# BBB_ADS1271_front_panel.net
KiCad netlist of a schematic drawn in EAGLE
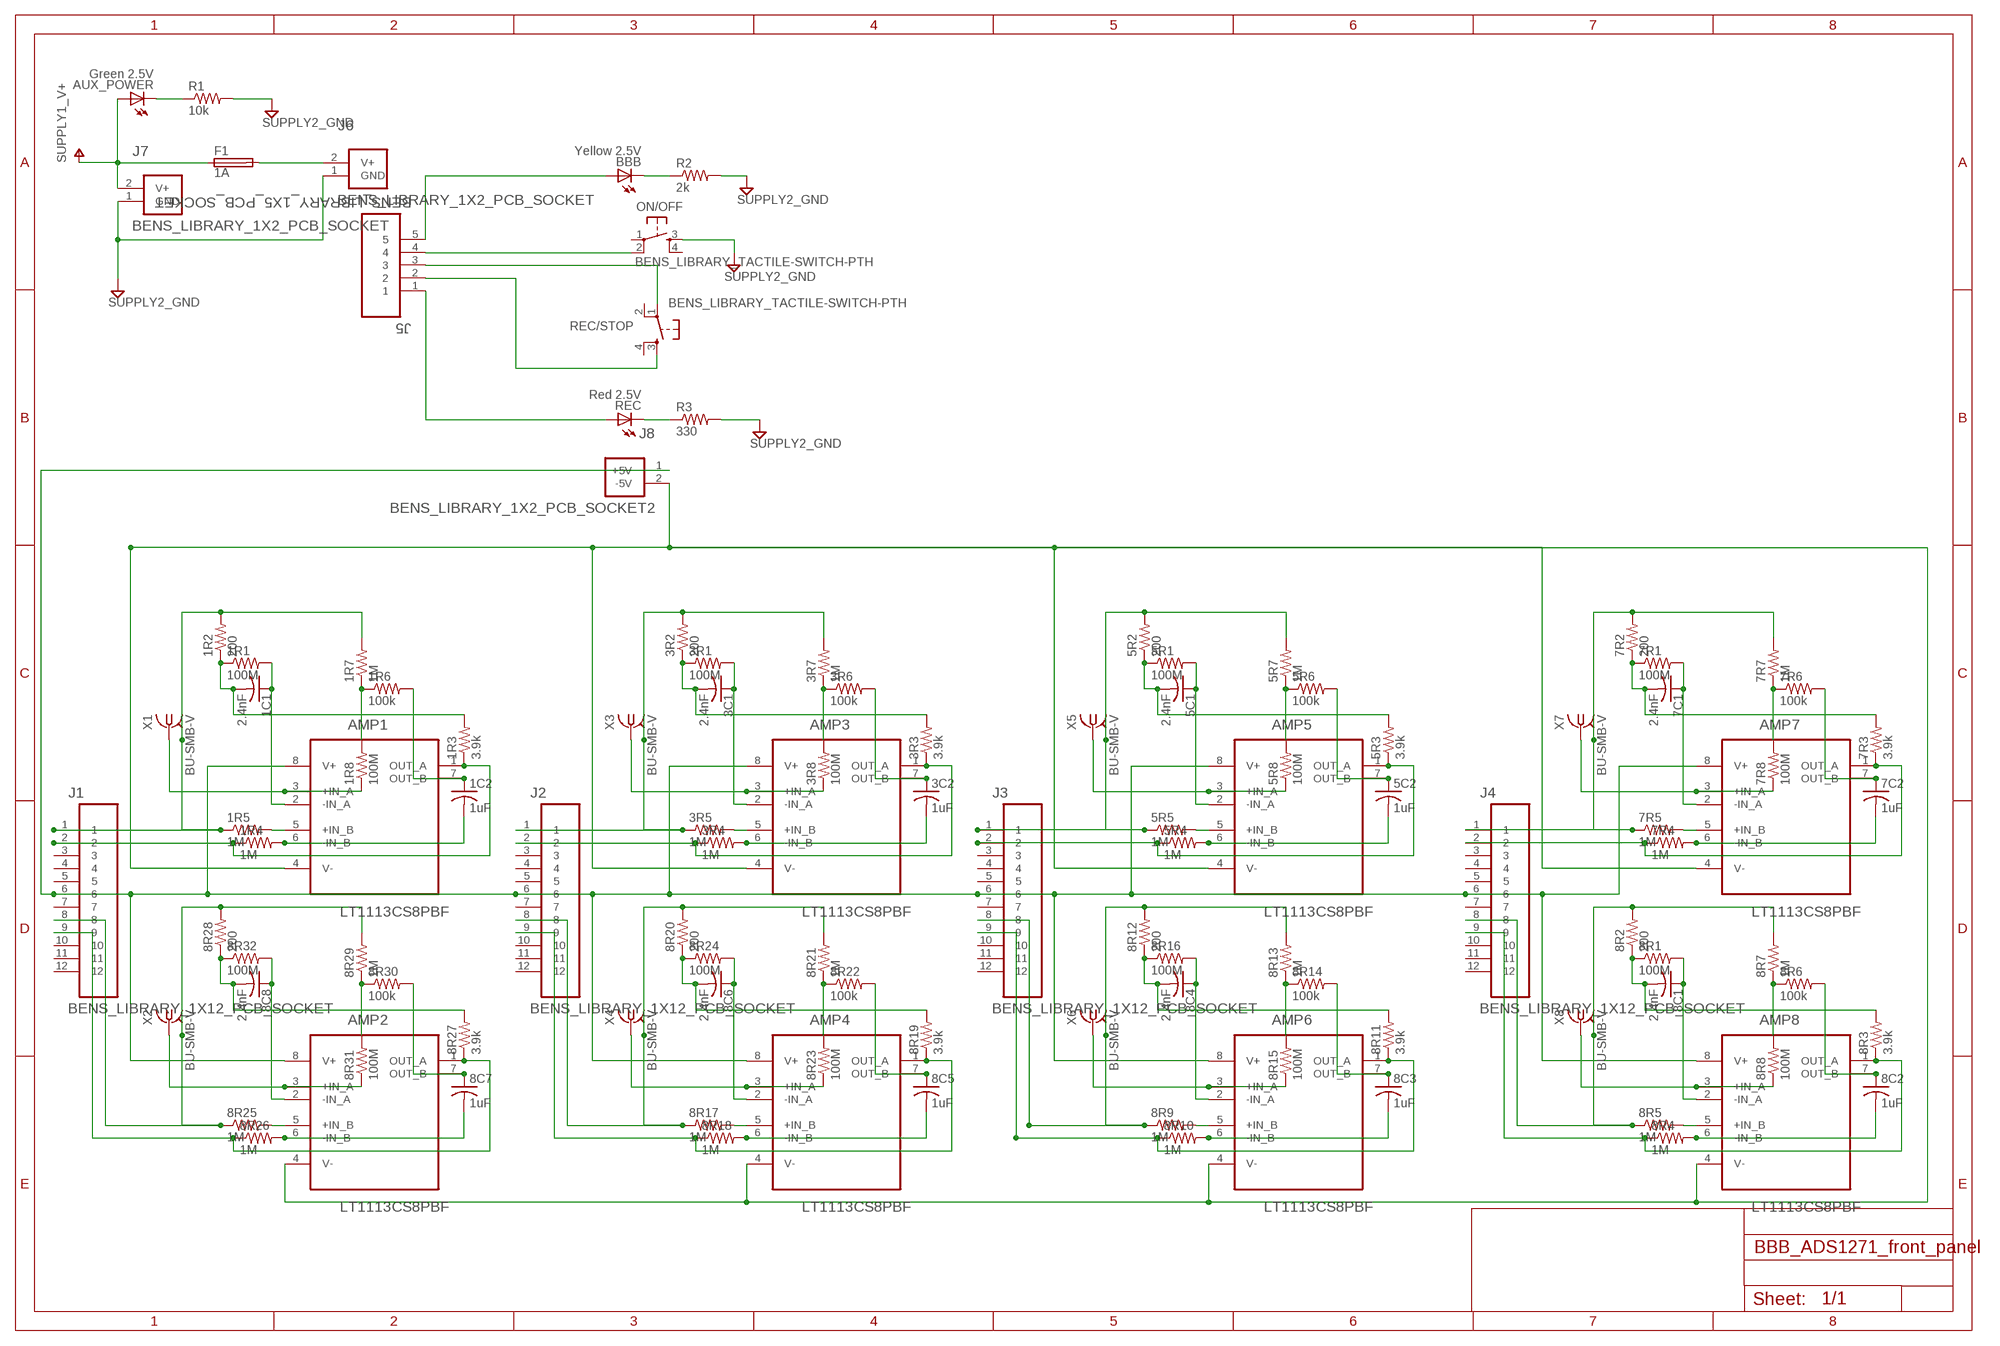
[diagram p0: schematic, sheet 1]

(export (version "E")
  (design (tool "Eeschema 10.0.6"))
  (components
    (comp (ref "1C1")
      (value "2.4nF")
      (footprint "eagle-import:ADAFRUIT_C0805K")
      (libsource (lib "eagle-import") (part "ADAFRUIT_C-USC0805K"))
    )
    (comp (ref "1C2")
      (value "1uF")
      (footprint "eagle-import:ADAFRUIT_C0805K")
      (libsource (lib "eagle-import") (part "ADAFRUIT_C-USC0805K"))
    )
    (comp (ref "1R1")
      (value "100M")
      (footprint "eagle-import:ADAFRUIT_R0805")
      (libsource (lib "eagle-import") (part "ADAFRUIT_R-US_R0805"))
    )
    (comp (ref "1R2")
      (value "200")
      (footprint "eagle-import:ADAFRUIT_R0805")
      (libsource (lib "eagle-import") (part "ADAFRUIT_R-US_R0805"))
    )
    (comp (ref "1R3")
      (value "3.9k")
      (footprint "eagle-import:ADAFRUIT_R0805")
      (libsource (lib "eagle-import") (part "ADAFRUIT_R-US_R0805"))
    )
    (comp (ref "1R4")
      (value "1M")
      (footprint "eagle-import:ADAFRUIT_R0805")
      (libsource (lib "eagle-import") (part "ADAFRUIT_R-US_R0805"))
    )
    (comp (ref "1R5")
      (value "1M")
      (footprint "eagle-import:ADAFRUIT_R0805")
      (libsource (lib "eagle-import") (part "ADAFRUIT_R-US_R0805"))
    )
    (comp (ref "1R6")
      (value "100k")
      (footprint "eagle-import:ADAFRUIT_R0805")
      (libsource (lib "eagle-import") (part "ADAFRUIT_R-US_R0805"))
    )
    (comp (ref "1R7")
      (value "1M")
      (footprint "eagle-import:ADAFRUIT_R0805")
      (libsource (lib "eagle-import") (part "ADAFRUIT_R-US_R0805"))
    )
    (comp (ref "1R8")
      (value "100M")
      (footprint "eagle-import:ADAFRUIT_R0805")
      (libsource (lib "eagle-import") (part "ADAFRUIT_R-US_R0805"))
    )
    (comp (ref "3C1")
      (value "2.4nF")
      (footprint "eagle-import:ADAFRUIT_C0805K")
      (libsource (lib "eagle-import") (part "ADAFRUIT_C-USC0805K"))
    )
    (comp (ref "3C2")
      (value "1uF")
      (footprint "eagle-import:ADAFRUIT_C0805K")
      (libsource (lib "eagle-import") (part "ADAFRUIT_C-USC0805K"))
    )
    (comp (ref "3R1")
      (value "100M")
      (footprint "eagle-import:ADAFRUIT_R0805")
      (libsource (lib "eagle-import") (part "ADAFRUIT_R-US_R0805"))
    )
    (comp (ref "3R2")
      (value "200")
      (footprint "eagle-import:ADAFRUIT_R0805")
      (libsource (lib "eagle-import") (part "ADAFRUIT_R-US_R0805"))
    )
    (comp (ref "3R3")
      (value "3.9k")
      (footprint "eagle-import:ADAFRUIT_R0805")
      (libsource (lib "eagle-import") (part "ADAFRUIT_R-US_R0805"))
    )
    (comp (ref "3R4")
      (value "1M")
      (footprint "eagle-import:ADAFRUIT_R0805")
      (libsource (lib "eagle-import") (part "ADAFRUIT_R-US_R0805"))
    )
    (comp (ref "3R5")
      (value "1M")
      (footprint "eagle-import:ADAFRUIT_R0805")
      (libsource (lib "eagle-import") (part "ADAFRUIT_R-US_R0805"))
    )
    (comp (ref "3R6")
      (value "100k")
      (footprint "eagle-import:ADAFRUIT_R0805")
      (libsource (lib "eagle-import") (part "ADAFRUIT_R-US_R0805"))
    )
    (comp (ref "3R7")
      (value "1M")
      (footprint "eagle-import:ADAFRUIT_R0805")
      (libsource (lib "eagle-import") (part "ADAFRUIT_R-US_R0805"))
    )
    (comp (ref "3R8")
      (value "100M")
      (footprint "eagle-import:ADAFRUIT_R0805")
      (libsource (lib "eagle-import") (part "ADAFRUIT_R-US_R0805"))
    )
    (comp (ref "5C1")
      (value "2.4nF")
      (footprint "eagle-import:ADAFRUIT_C0805K")
      (libsource (lib "eagle-import") (part "ADAFRUIT_C-USC0805K"))
    )
    (comp (ref "5C2")
      (value "1uF")
      (footprint "eagle-import:ADAFRUIT_C0805K")
      (libsource (lib "eagle-import") (part "ADAFRUIT_C-USC0805K"))
    )
    (comp (ref "5R1")
      (value "100M")
      (footprint "eagle-import:ADAFRUIT_R0805")
      (libsource (lib "eagle-import") (part "ADAFRUIT_R-US_R0805"))
    )
    (comp (ref "5R2")
      (value "200")
      (footprint "eagle-import:ADAFRUIT_R0805")
      (libsource (lib "eagle-import") (part "ADAFRUIT_R-US_R0805"))
    )
    (comp (ref "5R3")
      (value "3.9k")
      (footprint "eagle-import:ADAFRUIT_R0805")
      (libsource (lib "eagle-import") (part "ADAFRUIT_R-US_R0805"))
    )
    (comp (ref "5R4")
      (value "1M")
      (footprint "eagle-import:ADAFRUIT_R0805")
      (libsource (lib "eagle-import") (part "ADAFRUIT_R-US_R0805"))
    )
    (comp (ref "5R5")
      (value "1M")
      (footprint "eagle-import:ADAFRUIT_R0805")
      (libsource (lib "eagle-import") (part "ADAFRUIT_R-US_R0805"))
    )
    (comp (ref "5R6")
      (value "100k")
      (footprint "eagle-import:ADAFRUIT_R0805")
      (libsource (lib "eagle-import") (part "ADAFRUIT_R-US_R0805"))
    )
    (comp (ref "5R7")
      (value "1M")
      (footprint "eagle-import:ADAFRUIT_R0805")
      (libsource (lib "eagle-import") (part "ADAFRUIT_R-US_R0805"))
    )
    (comp (ref "5R8")
      (value "100M")
      (footprint "eagle-import:ADAFRUIT_R0805")
      (libsource (lib "eagle-import") (part "ADAFRUIT_R-US_R0805"))
    )
    (comp (ref "7C1")
      (value "2.4nF")
      (footprint "eagle-import:ADAFRUIT_C0805K")
      (libsource (lib "eagle-import") (part "ADAFRUIT_C-USC0805K"))
    )
    (comp (ref "7C2")
      (value "1uF")
      (footprint "eagle-import:ADAFRUIT_C0805K")
      (libsource (lib "eagle-import") (part "ADAFRUIT_C-USC0805K"))
    )
    (comp (ref "7R1")
      (value "100M")
      (footprint "eagle-import:ADAFRUIT_R0805")
      (libsource (lib "eagle-import") (part "ADAFRUIT_R-US_R0805"))
    )
    (comp (ref "7R2")
      (value "200")
      (footprint "eagle-import:ADAFRUIT_R0805")
      (libsource (lib "eagle-import") (part "ADAFRUIT_R-US_R0805"))
    )
    (comp (ref "7R3")
      (value "3.9k")
      (footprint "eagle-import:ADAFRUIT_R0805")
      (libsource (lib "eagle-import") (part "ADAFRUIT_R-US_R0805"))
    )
    (comp (ref "7R4")
      (value "1M")
      (footprint "eagle-import:ADAFRUIT_R0805")
      (libsource (lib "eagle-import") (part "ADAFRUIT_R-US_R0805"))
    )
    (comp (ref "7R5")
      (value "1M")
      (footprint "eagle-import:ADAFRUIT_R0805")
      (libsource (lib "eagle-import") (part "ADAFRUIT_R-US_R0805"))
    )
    (comp (ref "7R6")
      (value "100k")
      (footprint "eagle-import:ADAFRUIT_R0805")
      (libsource (lib "eagle-import") (part "ADAFRUIT_R-US_R0805"))
    )
    (comp (ref "7R7")
      (value "1M")
      (footprint "eagle-import:ADAFRUIT_R0805")
      (libsource (lib "eagle-import") (part "ADAFRUIT_R-US_R0805"))
    )
    (comp (ref "7R8")
      (value "100M")
      (footprint "eagle-import:ADAFRUIT_R0805")
      (libsource (lib "eagle-import") (part "ADAFRUIT_R-US_R0805"))
    )
    (comp (ref "8C1")
      (value "2.4nF")
      (footprint "eagle-import:ADAFRUIT_C0805K")
      (libsource (lib "eagle-import") (part "ADAFRUIT_C-USC0805K"))
    )
    (comp (ref "8C2")
      (value "1uF")
      (footprint "eagle-import:ADAFRUIT_C0805K")
      (libsource (lib "eagle-import") (part "ADAFRUIT_C-USC0805K"))
    )
    (comp (ref "8C3")
      (value "1uF")
      (footprint "eagle-import:ADAFRUIT_C0805K")
      (libsource (lib "eagle-import") (part "ADAFRUIT_C-USC0805K"))
    )
    (comp (ref "8C4")
      (value "2.4nF")
      (footprint "eagle-import:ADAFRUIT_C0805K")
      (libsource (lib "eagle-import") (part "ADAFRUIT_C-USC0805K"))
    )
    (comp (ref "8C5")
      (value "1uF")
      (footprint "eagle-import:ADAFRUIT_C0805K")
      (libsource (lib "eagle-import") (part "ADAFRUIT_C-USC0805K"))
    )
    (comp (ref "8C6")
      (value "2.4nF")
      (footprint "eagle-import:ADAFRUIT_C0805K")
      (libsource (lib "eagle-import") (part "ADAFRUIT_C-USC0805K"))
    )
    (comp (ref "8C7")
      (value "1uF")
      (footprint "eagle-import:ADAFRUIT_C0805K")
      (libsource (lib "eagle-import") (part "ADAFRUIT_C-USC0805K"))
    )
    (comp (ref "8C8")
      (value "2.4nF")
      (footprint "eagle-import:ADAFRUIT_C0805K")
      (libsource (lib "eagle-import") (part "ADAFRUIT_C-USC0805K"))
    )
    (comp (ref "8R1")
      (value "100M")
      (footprint "eagle-import:ADAFRUIT_R0805")
      (libsource (lib "eagle-import") (part "ADAFRUIT_R-US_R0805"))
    )
    (comp (ref "8R2")
      (value "200")
      (footprint "eagle-import:ADAFRUIT_R0805")
      (libsource (lib "eagle-import") (part "ADAFRUIT_R-US_R0805"))
    )
    (comp (ref "8R3")
      (value "3.9k")
      (footprint "eagle-import:ADAFRUIT_R0805")
      (libsource (lib "eagle-import") (part "ADAFRUIT_R-US_R0805"))
    )
    (comp (ref "8R4")
      (value "1M")
      (footprint "eagle-import:ADAFRUIT_R0805")
      (libsource (lib "eagle-import") (part "ADAFRUIT_R-US_R0805"))
    )
    (comp (ref "8R5")
      (value "1M")
      (footprint "eagle-import:ADAFRUIT_R0805")
      (libsource (lib "eagle-import") (part "ADAFRUIT_R-US_R0805"))
    )
    (comp (ref "8R6")
      (value "100k")
      (footprint "eagle-import:ADAFRUIT_R0805")
      (libsource (lib "eagle-import") (part "ADAFRUIT_R-US_R0805"))
    )
    (comp (ref "8R7")
      (value "1M")
      (footprint "eagle-import:ADAFRUIT_R0805")
      (libsource (lib "eagle-import") (part "ADAFRUIT_R-US_R0805"))
    )
    (comp (ref "8R8")
      (value "100M")
      (footprint "eagle-import:ADAFRUIT_R0805")
      (libsource (lib "eagle-import") (part "ADAFRUIT_R-US_R0805"))
    )
    (comp (ref "8R9")
      (value "1M")
      (footprint "eagle-import:ADAFRUIT_R0805")
      (libsource (lib "eagle-import") (part "ADAFRUIT_R-US_R0805"))
    )
    (comp (ref "8R10")
      (value "1M")
      (footprint "eagle-import:ADAFRUIT_R0805")
      (libsource (lib "eagle-import") (part "ADAFRUIT_R-US_R0805"))
    )
    (comp (ref "8R11")
      (value "3.9k")
      (footprint "eagle-import:ADAFRUIT_R0805")
      (libsource (lib "eagle-import") (part "ADAFRUIT_R-US_R0805"))
    )
    (comp (ref "8R12")
      (value "200")
      (footprint "eagle-import:ADAFRUIT_R0805")
      (libsource (lib "eagle-import") (part "ADAFRUIT_R-US_R0805"))
    )
    (comp (ref "8R13")
      (value "1M")
      (footprint "eagle-import:ADAFRUIT_R0805")
      (libsource (lib "eagle-import") (part "ADAFRUIT_R-US_R0805"))
    )
    (comp (ref "8R14")
      (value "100k")
      (footprint "eagle-import:ADAFRUIT_R0805")
      (libsource (lib "eagle-import") (part "ADAFRUIT_R-US_R0805"))
    )
    (comp (ref "8R15")
      (value "100M")
      (footprint "eagle-import:ADAFRUIT_R0805")
      (libsource (lib "eagle-import") (part "ADAFRUIT_R-US_R0805"))
    )
    (comp (ref "8R16")
      (value "100M")
      (footprint "eagle-import:ADAFRUIT_R0805")
      (libsource (lib "eagle-import") (part "ADAFRUIT_R-US_R0805"))
    )
    (comp (ref "8R17")
      (value "1M")
      (footprint "eagle-import:ADAFRUIT_R0805")
      (libsource (lib "eagle-import") (part "ADAFRUIT_R-US_R0805"))
    )
    (comp (ref "8R18")
      (value "1M")
      (footprint "eagle-import:ADAFRUIT_R0805")
      (libsource (lib "eagle-import") (part "ADAFRUIT_R-US_R0805"))
    )
    (comp (ref "8R19")
      (value "3.9k")
      (footprint "eagle-import:ADAFRUIT_R0805")
      (libsource (lib "eagle-import") (part "ADAFRUIT_R-US_R0805"))
    )
    (comp (ref "8R20")
      (value "200")
      (footprint "eagle-import:ADAFRUIT_R0805")
      (libsource (lib "eagle-import") (part "ADAFRUIT_R-US_R0805"))
    )
    (comp (ref "8R21")
      (value "1M")
      (footprint "eagle-import:ADAFRUIT_R0805")
      (libsource (lib "eagle-import") (part "ADAFRUIT_R-US_R0805"))
    )
    (comp (ref "8R22")
      (value "100k")
      (footprint "eagle-import:ADAFRUIT_R0805")
      (libsource (lib "eagle-import") (part "ADAFRUIT_R-US_R0805"))
    )
    (comp (ref "8R23")
      (value "100M")
      (footprint "eagle-import:ADAFRUIT_R0805")
      (libsource (lib "eagle-import") (part "ADAFRUIT_R-US_R0805"))
    )
    (comp (ref "8R24")
      (value "100M")
      (footprint "eagle-import:ADAFRUIT_R0805")
      (libsource (lib "eagle-import") (part "ADAFRUIT_R-US_R0805"))
    )
    (comp (ref "8R25")
      (value "1M")
      (footprint "eagle-import:ADAFRUIT_R0805")
      (libsource (lib "eagle-import") (part "ADAFRUIT_R-US_R0805"))
    )
    (comp (ref "8R26")
      (value "1M")
      (footprint "eagle-import:ADAFRUIT_R0805")
      (libsource (lib "eagle-import") (part "ADAFRUIT_R-US_R0805"))
    )
    (comp (ref "8R27")
      (value "3.9k")
      (footprint "eagle-import:ADAFRUIT_R0805")
      (libsource (lib "eagle-import") (part "ADAFRUIT_R-US_R0805"))
    )
    (comp (ref "8R28")
      (value "200")
      (footprint "eagle-import:ADAFRUIT_R0805")
      (libsource (lib "eagle-import") (part "ADAFRUIT_R-US_R0805"))
    )
    (comp (ref "8R29")
      (value "1M")
      (footprint "eagle-import:ADAFRUIT_R0805")
      (libsource (lib "eagle-import") (part "ADAFRUIT_R-US_R0805"))
    )
    (comp (ref "8R30")
      (value "100k")
      (footprint "eagle-import:ADAFRUIT_R0805")
      (libsource (lib "eagle-import") (part "ADAFRUIT_R-US_R0805"))
    )
    (comp (ref "8R31")
      (value "100M")
      (footprint "eagle-import:ADAFRUIT_R0805")
      (libsource (lib "eagle-import") (part "ADAFRUIT_R-US_R0805"))
    )
    (comp (ref "8R32")
      (value "100M")
      (footprint "eagle-import:ADAFRUIT_R0805")
      (libsource (lib "eagle-import") (part "ADAFRUIT_R-US_R0805"))
    )
    (comp (ref "AMP1")
      (value "LT1113CS8PBF")
      (footprint "eagle-import:SOIC127P600X175-8N")
      (fields (field (name "MPN") "LT1113CS8#PBF"))
      (libsource (lib "eagle-import") (part "LT1113CS8PBF"))
    )
    (comp (ref "AMP2")
      (value "LT1113CS8PBF")
      (footprint "eagle-import:SOIC127P600X175-8N")
      (fields (field (name "MPN") "LT1113CS8#PBF"))
      (libsource (lib "eagle-import") (part "LT1113CS8PBF"))
    )
    (comp (ref "AMP3")
      (value "LT1113CS8PBF")
      (footprint "eagle-import:SOIC127P600X175-8N")
      (fields (field (name "MPN") "LT1113CS8#PBF"))
      (libsource (lib "eagle-import") (part "LT1113CS8PBF"))
    )
    (comp (ref "AMP4")
      (value "LT1113CS8PBF")
      (footprint "eagle-import:SOIC127P600X175-8N")
      (fields (field (name "MPN") "LT1113CS8#PBF"))
      (libsource (lib "eagle-import") (part "LT1113CS8PBF"))
    )
    (comp (ref "AMP5")
      (value "LT1113CS8PBF")
      (footprint "eagle-import:SOIC127P600X175-8N")
      (fields (field (name "MPN") "LT1113CS8#PBF"))
      (libsource (lib "eagle-import") (part "LT1113CS8PBF"))
    )
    (comp (ref "AMP6")
      (value "LT1113CS8PBF")
      (footprint "eagle-import:SOIC127P600X175-8N")
      (fields (field (name "MPN") "LT1113CS8#PBF"))
      (libsource (lib "eagle-import") (part "LT1113CS8PBF"))
    )
    (comp (ref "AMP7")
      (value "LT1113CS8PBF")
      (footprint "eagle-import:SOIC127P600X175-8N")
      (fields (field (name "MPN") "LT1113CS8#PBF"))
      (libsource (lib "eagle-import") (part "LT1113CS8PBF"))
    )
    (comp (ref "AMP8")
      (value "LT1113CS8PBF")
      (footprint "eagle-import:SOIC127P600X175-8N")
      (fields (field (name "MPN") "LT1113CS8#PBF"))
      (libsource (lib "eagle-import") (part "LT1113CS8PBF"))
    )
    (comp (ref "AUX_POWER")
      (value "Green 2.5V")
      (footprint "eagle-import:ADAFRUIT_LED5MM")
      (libsource (lib "eagle-import") (part "ADAFRUIT_LED5MM"))
    )
    (comp (ref "BBB")
      (value "Yellow 2.5V")
      (footprint "eagle-import:ADAFRUIT_LED5MM")
      (libsource (lib "eagle-import") (part "ADAFRUIT_LED5MM"))
    )
    (comp (ref "F1")
      (value "1A")
      (footprint "eagle-import:LITTLEFUSE_PACKAGE")
      (libsource (lib "eagle-import") (part "LITTLEFUSE_SMD"))
    )
    (comp (ref "J1")
      (value "BENS_LIBRARY_1X12_PCB_SOCKET")
      (footprint "eagle-import:BENS_LIBRARY_SAMTEC_SSM-112-L-DV-BE")
      (fields (field (name "MPN") "SSM-112-L-DV-BE"))
      (libsource (lib "eagle-import") (part "BENS_LIBRARY_1X12_PCB_SOCKET"))
    )
    (comp (ref "J2")
      (value "BENS_LIBRARY_1X12_PCB_SOCKET")
      (footprint "eagle-import:BENS_LIBRARY_SAMTEC_SSM-112-L-DV-BE")
      (fields (field (name "MPN") "SSM-112-L-DV-BE"))
      (libsource (lib "eagle-import") (part "BENS_LIBRARY_1X12_PCB_SOCKET"))
    )
    (comp (ref "J3")
      (value "BENS_LIBRARY_1X12_PCB_SOCKET")
      (footprint "eagle-import:BENS_LIBRARY_SAMTEC_SSM-112-L-DV-BE")
      (fields (field (name "MPN") "SSM-112-L-DV-BE"))
      (libsource (lib "eagle-import") (part "BENS_LIBRARY_1X12_PCB_SOCKET"))
    )
    (comp (ref "J4")
      (value "BENS_LIBRARY_1X12_PCB_SOCKET")
      (footprint "eagle-import:BENS_LIBRARY_SAMTEC_SSM-112-L-DV-BE")
      (fields (field (name "MPN") "SSM-112-L-DV-BE"))
      (libsource (lib "eagle-import") (part "BENS_LIBRARY_1X12_PCB_SOCKET"))
    )
    (comp (ref "J5")
      (value "BENS_LIBRARY_1X5_PCB_SOCKET")
      (footprint "eagle-import:BENS_LIBRARY_SAMTEC_SSM-15-L-DV-BE")
      (libsource (lib "eagle-import") (part "BENS_LIBRARY_1X5_PCB_SOCKET"))
    )
    (comp (ref "J6")
      (value "BENS_LIBRARY_1X2_PCB_SOCKET")
      (footprint "eagle-import:BENS_LIBRARY_1X2_PCB_SOCKET")
      (libsource (lib "eagle-import") (part "BENS_LIBRARY_1X2_PCB_SOCKET"))
    )
    (comp (ref "J7")
      (value "BENS_LIBRARY_1X2_PCB_SOCKET")
      (footprint "eagle-import:BENS_LIBRARY_1X2_PCB_SOCKET")
      (libsource (lib "eagle-import") (part "BENS_LIBRARY_1X2_PCB_SOCKET"))
    )
    (comp (ref "J8")
      (value "BENS_LIBRARY_1X2_PCB_SOCKET2")
      (footprint "eagle-import:BENS_LIBRARY_1X2_PCB_SOCKET2")
      (libsource (lib "eagle-import") (part "BENS_LIBRARY_1X2_PCB_SOCKET2"))
    )
    (comp (ref "ON/OFF")
      (value "BENS_LIBRARY_TACTILE-SWITCH-PTH")
      (footprint "eagle-import:BENS_LIBRARY_TAC-SWITCH-PTH")
      (libsource (lib "eagle-import") (part "BENS_LIBRARY_TACTILE-SWITCH-PTH"))
    )
    (comp (ref "R1")
      (value "10k")
      (footprint "eagle-import:ADAFRUIT_R0805")
      (libsource (lib "eagle-import") (part "ADAFRUIT_R-US_R0805"))
    )
    (comp (ref "R2")
      (value "2k")
      (footprint "eagle-import:ADAFRUIT_R0805")
      (libsource (lib "eagle-import") (part "ADAFRUIT_R-US_R0805"))
    )
    (comp (ref "R3")
      (value "330")
      (footprint "eagle-import:ADAFRUIT_R0805")
      (libsource (lib "eagle-import") (part "ADAFRUIT_R-US_R0805"))
    )
    (comp (ref "REC")
      (value "Red 2.5V")
      (footprint "eagle-import:ADAFRUIT_LED5MM")
      (libsource (lib "eagle-import") (part "ADAFRUIT_LED5MM"))
    )
    (comp (ref "REC/STOP")
      (value "BENS_LIBRARY_TACTILE-SWITCH-PTH")
      (footprint "eagle-import:BENS_LIBRARY_TAC-SWITCH-PTH")
      (libsource (lib "eagle-import") (part "BENS_LIBRARY_TACTILE-SWITCH-PTH"))
    )
    (comp (ref "X1")
      (value "BU-SMB-V")
      (footprint "eagle-import:BU-SMB-V")
      (libsource (lib "eagle-import") (part "BU-SMB-V"))
    )
    (comp (ref "X2")
      (value "BU-SMB-V")
      (footprint "eagle-import:BU-SMB-V")
      (libsource (lib "eagle-import") (part "BU-SMB-V"))
    )
    (comp (ref "X3")
      (value "BU-SMB-V")
      (footprint "eagle-import:BU-SMB-V")
      (libsource (lib "eagle-import") (part "BU-SMB-V"))
    )
    (comp (ref "X4")
      (value "BU-SMB-V")
      (footprint "eagle-import:BU-SMB-V")
      (libsource (lib "eagle-import") (part "BU-SMB-V"))
    )
    (comp (ref "X5")
      (value "BU-SMB-V")
      (footprint "eagle-import:BU-SMB-V")
      (libsource (lib "eagle-import") (part "BU-SMB-V"))
    )
    (comp (ref "X6")
      (value "BU-SMB-V")
      (footprint "eagle-import:BU-SMB-V")
      (libsource (lib "eagle-import") (part "BU-SMB-V"))
    )
    (comp (ref "X7")
      (value "BU-SMB-V")
      (footprint "eagle-import:BU-SMB-V")
      (libsource (lib "eagle-import") (part "BU-SMB-V"))
    )
    (comp (ref "X8")
      (value "BU-SMB-V")
      (footprint "eagle-import:BU-SMB-V")
      (libsource (lib "eagle-import") (part "BU-SMB-V"))
    )
  )
  (nets
    (net (code "1") (name "Net-(1C1-Pad2)") (class "Default")
      (node (ref "1C1") (pin "2") (pinfunction "2_2") (pintype "passive"))
      (node (ref "1R1") (pin "1") (pinfunction "1_1") (pintype "passive"))
      (node (ref "1R2") (pin "1") (pinfunction "1_1") (pintype "passive"))
      (node (ref "1R3") (pin "2") (pinfunction "2_2") (pintype "passive"))
    )
    (net (code "2") (name "Net-(1R2-Pad2)") (class "Default")
      (node (ref "1R2") (pin "2") (pinfunction "2_2") (pintype "passive"))
      (node (ref "1R5") (pin "1") (pinfunction "1_1") (pintype "passive"))
      (node (ref "1R7") (pin "2") (pinfunction "2_2") (pintype "passive"))
      (node (ref "J1") (pin "1") (pinfunction "1_1") (pintype "passive"))
      (node (ref "X1") (pin "2") (pinfunction "2_2") (pintype "passive"))
      (node (ref "X1") (pin "3") (pinfunction "2_3") (pintype "passive"))
      (node (ref "X1") (pin "4") (pinfunction "2_4") (pintype "passive"))
      (node (ref "X1") (pin "5") (pinfunction "2_5") (pintype "passive"))
    )
    (net (code "3") (name "Net-(1R6-Pad1)") (class "Default")
      (node (ref "1R6") (pin "1") (pinfunction "1_1") (pintype "passive"))
      (node (ref "1R7") (pin "1") (pinfunction "1_1") (pintype "passive"))
      (node (ref "1R8") (pin "2") (pinfunction "2_2") (pintype "passive"))
    )
    (net (code "4") (name "Net-(3C1-Pad2)") (class "Default")
      (node (ref "3C1") (pin "2") (pinfunction "2_2") (pintype "passive"))
      (node (ref "3R1") (pin "1") (pinfunction "1_1") (pintype "passive"))
      (node (ref "3R2") (pin "1") (pinfunction "1_1") (pintype "passive"))
      (node (ref "3R3") (pin "2") (pinfunction "2_2") (pintype "passive"))
    )
    (net (code "5") (name "Net-(3R2-Pad2)") (class "Default")
      (node (ref "3R2") (pin "2") (pinfunction "2_2") (pintype "passive"))
      (node (ref "3R5") (pin "1") (pinfunction "1_1") (pintype "passive"))
      (node (ref "3R7") (pin "2") (pinfunction "2_2") (pintype "passive"))
      (node (ref "J2") (pin "1") (pinfunction "1_1") (pintype "passive"))
      (node (ref "X3") (pin "2") (pinfunction "2_2") (pintype "passive"))
      (node (ref "X3") (pin "3") (pinfunction "2_3") (pintype "passive"))
      (node (ref "X3") (pin "4") (pinfunction "2_4") (pintype "passive"))
      (node (ref "X3") (pin "5") (pinfunction "2_5") (pintype "passive"))
    )
    (net (code "6") (name "Net-(3R6-Pad1)") (class "Default")
      (node (ref "3R6") (pin "1") (pinfunction "1_1") (pintype "passive"))
      (node (ref "3R7") (pin "1") (pinfunction "1_1") (pintype "passive"))
      (node (ref "3R8") (pin "2") (pinfunction "2_2") (pintype "passive"))
    )
    (net (code "7") (name "Net-(5C1-Pad2)") (class "Default")
      (node (ref "5C1") (pin "2") (pinfunction "2_2") (pintype "passive"))
      (node (ref "5R1") (pin "1") (pinfunction "1_1") (pintype "passive"))
      (node (ref "5R2") (pin "1") (pinfunction "1_1") (pintype "passive"))
      (node (ref "5R3") (pin "2") (pinfunction "2_2") (pintype "passive"))
    )
    (net (code "8") (name "Net-(5R2-Pad2)") (class "Default")
      (node (ref "5R2") (pin "2") (pinfunction "2_2") (pintype "passive"))
      (node (ref "5R5") (pin "1") (pinfunction "1_1") (pintype "passive"))
      (node (ref "5R7") (pin "2") (pinfunction "2_2") (pintype "passive"))
      (node (ref "J3") (pin "1") (pinfunction "1_1") (pintype "passive"))
      (node (ref "X5") (pin "2") (pinfunction "2_2") (pintype "passive"))
      (node (ref "X5") (pin "3") (pinfunction "2_3") (pintype "passive"))
      (node (ref "X5") (pin "4") (pinfunction "2_4") (pintype "passive"))
      (node (ref "X5") (pin "5") (pinfunction "2_5") (pintype "passive"))
    )
    (net (code "9") (name "Net-(5R6-Pad1)") (class "Default")
      (node (ref "5R6") (pin "1") (pinfunction "1_1") (pintype "passive"))
      (node (ref "5R7") (pin "1") (pinfunction "1_1") (pintype "passive"))
      (node (ref "5R8") (pin "2") (pinfunction "2_2") (pintype "passive"))
    )
    (net (code "10") (name "Net-(7C1-Pad2)") (class "Default")
      (node (ref "7C1") (pin "2") (pinfunction "2_2") (pintype "passive"))
      (node (ref "7R1") (pin "1") (pinfunction "1_1") (pintype "passive"))
      (node (ref "7R2") (pin "1") (pinfunction "1_1") (pintype "passive"))
      (node (ref "7R3") (pin "2") (pinfunction "2_2") (pintype "passive"))
    )
    (net (code "11") (name "Net-(7R2-Pad2)") (class "Default")
      (node (ref "7R2") (pin "2") (pinfunction "2_2") (pintype "passive"))
      (node (ref "7R5") (pin "1") (pinfunction "1_1") (pintype "passive"))
      (node (ref "7R7") (pin "2") (pinfunction "2_2") (pintype "passive"))
      (node (ref "J4") (pin "1") (pinfunction "1_1") (pintype "passive"))
      (node (ref "X7") (pin "2") (pinfunction "2_2") (pintype "passive"))
      (node (ref "X7") (pin "3") (pinfunction "2_3") (pintype "passive"))
      (node (ref "X7") (pin "4") (pinfunction "2_4") (pintype "passive"))
      (node (ref "X7") (pin "5") (pinfunction "2_5") (pintype "passive"))
    )
    (net (code "12") (name "Net-(7R6-Pad1)") (class "Default")
      (node (ref "7R6") (pin "1") (pinfunction "1_1") (pintype "passive"))
      (node (ref "7R7") (pin "1") (pinfunction "1_1") (pintype "passive"))
      (node (ref "7R8") (pin "2") (pinfunction "2_2") (pintype "passive"))
    )
    (net (code "13") (name "Net-(8C1-Pad2)") (class "Default")
      (node (ref "8C1") (pin "2") (pinfunction "2_2") (pintype "passive"))
      (node (ref "8R1") (pin "1") (pinfunction "1_1") (pintype "passive"))
      (node (ref "8R2") (pin "1") (pinfunction "1_1") (pintype "passive"))
      (node (ref "8R3") (pin "2") (pinfunction "2_2") (pintype "passive"))
    )
    (net (code "14") (name "Net-(8C4-Pad2)") (class "Default")
      (node (ref "8C4") (pin "2") (pinfunction "2_2") (pintype "passive"))
      (node (ref "8R11") (pin "2") (pinfunction "2_2") (pintype "passive"))
      (node (ref "8R12") (pin "1") (pinfunction "1_1") (pintype "passive"))
      (node (ref "8R16") (pin "1") (pinfunction "1_1") (pintype "passive"))
    )
    (net (code "15") (name "Net-(8C6-Pad2)") (class "Default")
      (node (ref "8C6") (pin "2") (pinfunction "2_2") (pintype "passive"))
      (node (ref "8R19") (pin "2") (pinfunction "2_2") (pintype "passive"))
      (node (ref "8R20") (pin "1") (pinfunction "1_1") (pintype "passive"))
      (node (ref "8R24") (pin "1") (pinfunction "1_1") (pintype "passive"))
    )
    (net (code "16") (name "Net-(8C8-Pad2)") (class "Default")
      (node (ref "8C8") (pin "2") (pinfunction "2_2") (pintype "passive"))
      (node (ref "8R27") (pin "2") (pinfunction "2_2") (pintype "passive"))
      (node (ref "8R28") (pin "1") (pinfunction "1_1") (pintype "passive"))
      (node (ref "8R32") (pin "1") (pinfunction "1_1") (pintype "passive"))
    )
    (net (code "17") (name "Net-(8R2-Pad2)") (class "Default")
      (node (ref "8R2") (pin "2") (pinfunction "2_2") (pintype "passive"))
      (node (ref "8R5") (pin "1") (pinfunction "1_1") (pintype "passive"))
      (node (ref "8R7") (pin "2") (pinfunction "2_2") (pintype "passive"))
      (node (ref "J4") (pin "8") (pinfunction "8_8") (pintype "passive"))
      (node (ref "X8") (pin "2") (pinfunction "2_2") (pintype "passive"))
      (node (ref "X8") (pin "3") (pinfunction "2_3") (pintype "passive"))
      (node (ref "X8") (pin "4") (pinfunction "2_4") (pintype "passive"))
      (node (ref "X8") (pin "5") (pinfunction "2_5") (pintype "passive"))
    )
    (net (code "18") (name "Net-(8R6-Pad1)") (class "Default")
      (node (ref "8R6") (pin "1") (pinfunction "1_1") (pintype "passive"))
      (node (ref "8R7") (pin "1") (pinfunction "1_1") (pintype "passive"))
      (node (ref "8R8") (pin "2") (pinfunction "2_2") (pintype "passive"))
    )
    (net (code "19") (name "Net-(8R12-Pad2)") (class "Default")
      (node (ref "8R12") (pin "2") (pinfunction "2_2") (pintype "passive"))
      (node (ref "8R13") (pin "2") (pinfunction "2_2") (pintype "passive"))
      (node (ref "8R9") (pin "1") (pinfunction "1_1") (pintype "passive"))
      (node (ref "J3") (pin "8") (pinfunction "8_8") (pintype "passive"))
      (node (ref "X6") (pin "2") (pinfunction "2_2") (pintype "passive"))
      (node (ref "X6") (pin "3") (pinfunction "2_3") (pintype "passive"))
      (node (ref "X6") (pin "4") (pinfunction "2_4") (pintype "passive"))
      (node (ref "X6") (pin "5") (pinfunction "2_5") (pintype "passive"))
    )
    (net (code "20") (name "Net-(8R13-Pad1)") (class "Default")
      (node (ref "8R13") (pin "1") (pinfunction "1_1") (pintype "passive"))
      (node (ref "8R14") (pin "1") (pinfunction "1_1") (pintype "passive"))
      (node (ref "8R15") (pin "2") (pinfunction "2_2") (pintype "passive"))
    )
    (net (code "21") (name "Net-(8R17-Pad1)") (class "Default")
      (node (ref "8R17") (pin "1") (pinfunction "1_1") (pintype "passive"))
      (node (ref "8R20") (pin "2") (pinfunction "2_2") (pintype "passive"))
      (node (ref "8R21") (pin "2") (pinfunction "2_2") (pintype "passive"))
      (node (ref "J2") (pin "8") (pinfunction "8_8") (pintype "passive"))
      (node (ref "X4") (pin "2") (pinfunction "2_2") (pintype "passive"))
      (node (ref "X4") (pin "3") (pinfunction "2_3") (pintype "passive"))
      (node (ref "X4") (pin "4") (pinfunction "2_4") (pintype "passive"))
      (node (ref "X4") (pin "5") (pinfunction "2_5") (pintype "passive"))
    )
    (net (code "22") (name "Net-(8R21-Pad1)") (class "Default")
      (node (ref "8R21") (pin "1") (pinfunction "1_1") (pintype "passive"))
      (node (ref "8R22") (pin "1") (pinfunction "1_1") (pintype "passive"))
      (node (ref "8R23") (pin "2") (pinfunction "2_2") (pintype "passive"))
    )
    (net (code "23") (name "Net-(8R25-Pad1)") (class "Default")
      (node (ref "8R25") (pin "1") (pinfunction "1_1") (pintype "passive"))
      (node (ref "8R28") (pin "2") (pinfunction "2_2") (pintype "passive"))
      (node (ref "8R29") (pin "2") (pinfunction "2_2") (pintype "passive"))
      (node (ref "J1") (pin "8") (pinfunction "8_8") (pintype "passive"))
      (node (ref "X2") (pin "2") (pinfunction "2_2") (pintype "passive"))
      (node (ref "X2") (pin "3") (pinfunction "2_3") (pintype "passive"))
      (node (ref "X2") (pin "4") (pinfunction "2_4") (pintype "passive"))
      (node (ref "X2") (pin "5") (pinfunction "2_5") (pintype "passive"))
    )
    (net (code "24") (name "Net-(8R29-Pad1)") (class "Default")
      (node (ref "8R29") (pin "1") (pinfunction "1_1") (pintype "passive"))
      (node (ref "8R30") (pin "1") (pinfunction "1_1") (pintype "passive"))
      (node (ref "8R31") (pin "2") (pinfunction "2_2") (pintype "passive"))
    )
    (net (code "25") (name "Net-(AMP1-+IN_A)") (class "Default")
      (node (ref "1R8") (pin "1") (pinfunction "1_1") (pintype "passive"))
      (node (ref "AMP1") (pin "3") (pinfunction "+IN_A_3") (pintype "input"))
      (node (ref "X1") (pin "1") (pinfunction "1_1") (pintype "passive"))
    )
    (net (code "26") (name "Net-(AMP1-+IN_B)") (class "Default")
      (node (ref "1R5") (pin "2") (pinfunction "2_2") (pintype "passive"))
      (node (ref "AMP1") (pin "5") (pinfunction "+IN_B_5") (pintype "input"))
    )
    (net (code "27") (name "Net-(AMP1--IN_A)") (class "Default")
      (node (ref "1C1") (pin "1") (pinfunction "1_1") (pintype "passive"))
      (node (ref "1R1") (pin "2") (pinfunction "2_2") (pintype "passive"))
      (node (ref "AMP1") (pin "2") (pinfunction "-IN_A_2") (pintype "input"))
    )
    (net (code "28") (name "Net-(AMP1--IN_B)") (class "Default")
      (node (ref "1C2") (pin "2") (pinfunction "2_2") (pintype "passive"))
      (node (ref "1R4") (pin "2") (pinfunction "2_2") (pintype "passive"))
      (node (ref "AMP1") (pin "6") (pinfunction "-IN_B_6") (pintype "input"))
    )
    (net (code "29") (name "Net-(AMP1-OUT_A)") (class "Default")
      (node (ref "1R3") (pin "1") (pinfunction "1_1") (pintype "passive"))
      (node (ref "1R4") (pin "1") (pinfunction "1_1") (pintype "passive"))
      (node (ref "AMP1") (pin "1") (pinfunction "OUT_A_1") (pintype "output"))
      (node (ref "J1") (pin "2") (pinfunction "2_2") (pintype "passive"))
    )
    (net (code "30") (name "Net-(AMP1-OUT_B)") (class "Default")
      (node (ref "1C2") (pin "1") (pinfunction "1_1") (pintype "passive"))
      (node (ref "1R6") (pin "2") (pinfunction "2_2") (pintype "passive"))
      (node (ref "AMP1") (pin "7") (pinfunction "OUT_B_7") (pintype "output"))
    )
    (net (code "31") (name "Net-(AMP1-V+)") (class "Default")
      (node (ref "AMP1") (pin "8") (pinfunction "V+_8") (pintype "power_in"))
      (node (ref "AMP2") (pin "8") (pinfunction "V+_8") (pintype "power_in"))
      (node (ref "AMP3") (pin "8") (pinfunction "V+_8") (pintype "power_in"))
      (node (ref "AMP4") (pin "8") (pinfunction "V+_8") (pintype "power_in"))
      (node (ref "AMP5") (pin "8") (pinfunction "V+_8") (pintype "power_in"))
      (node (ref "AMP6") (pin "8") (pinfunction "V+_8") (pintype "power_in"))
      (node (ref "AMP7") (pin "8") (pinfunction "V+_8") (pintype "power_in"))
      (node (ref "AMP8") (pin "8") (pinfunction "V+_8") (pintype "power_in"))
      (node (ref "J1") (pin "6") (pinfunction "6_6") (pintype "passive"))
      (node (ref "J2") (pin "6") (pinfunction "6_6") (pintype "passive"))
      (node (ref "J3") (pin "6") (pinfunction "6_6") (pintype "passive"))
      (node (ref "J4") (pin "6") (pinfunction "6_6") (pintype "passive"))
      (node (ref "J8") (pin "1") (pinfunction "+5V_1") (pintype "power_in"))
    )
    (net (code "32") (name "Net-(AMP1-V-)") (class "Default")
      (node (ref "AMP1") (pin "4") (pinfunction "V-_4") (pintype "power_in"))
      (node (ref "AMP2") (pin "4") (pinfunction "V-_4") (pintype "power_in"))
      (node (ref "AMP3") (pin "4") (pinfunction "V-_4") (pintype "power_in"))
      (node (ref "AMP4") (pin "4") (pinfunction "V-_4") (pintype "power_in"))
      (node (ref "AMP5") (pin "4") (pinfunction "V-_4") (pintype "power_in"))
      (node (ref "AMP6") (pin "4") (pinfunction "V-_4") (pintype "power_in"))
      (node (ref "AMP7") (pin "4") (pinfunction "V-_4") (pintype "power_in"))
      (node (ref "AMP8") (pin "4") (pinfunction "V-_4") (pintype "power_in"))
      (node (ref "J8") (pin "2") (pinfunction "-5V_2") (pintype "power_in"))
    )
    (net (code "33") (name "Net-(AMP2-+IN_A)") (class "Default")
      (node (ref "8R31") (pin "1") (pinfunction "1_1") (pintype "passive"))
      (node (ref "AMP2") (pin "3") (pinfunction "+IN_A_3") (pintype "input"))
      (node (ref "X2") (pin "1") (pinfunction "1_1") (pintype "passive"))
    )
    (net (code "34") (name "Net-(AMP2-+IN_B)") (class "Default")
      (node (ref "8R25") (pin "2") (pinfunction "2_2") (pintype "passive"))
      (node (ref "AMP2") (pin "5") (pinfunction "+IN_B_5") (pintype "input"))
    )
    (net (code "35") (name "Net-(AMP2--IN_A)") (class "Default")
      (node (ref "8C8") (pin "1") (pinfunction "1_1") (pintype "passive"))
      (node (ref "8R32") (pin "2") (pinfunction "2_2") (pintype "passive"))
      (node (ref "AMP2") (pin "2") (pinfunction "-IN_A_2") (pintype "input"))
    )
    (net (code "36") (name "Net-(AMP2--IN_B)") (class "Default")
      (node (ref "8C7") (pin "2") (pinfunction "2_2") (pintype "passive"))
      (node (ref "8R26") (pin "2") (pinfunction "2_2") (pintype "passive"))
      (node (ref "AMP2") (pin "6") (pinfunction "-IN_B_6") (pintype "input"))
    )
    (net (code "37") (name "Net-(AMP2-OUT_A)") (class "Default")
      (node (ref "8R26") (pin "1") (pinfunction "1_1") (pintype "passive"))
      (node (ref "8R27") (pin "1") (pinfunction "1_1") (pintype "passive"))
      (node (ref "AMP2") (pin "1") (pinfunction "OUT_A_1") (pintype "output"))
      (node (ref "J1") (pin "9") (pinfunction "9_9") (pintype "passive"))
    )
    (net (code "38") (name "Net-(AMP2-OUT_B)") (class "Default")
      (node (ref "8C7") (pin "1") (pinfunction "1_1") (pintype "passive"))
      (node (ref "8R30") (pin "2") (pinfunction "2_2") (pintype "passive"))
      (node (ref "AMP2") (pin "7") (pinfunction "OUT_B_7") (pintype "output"))
    )
    (net (code "39") (name "Net-(AMP3-+IN_A)") (class "Default")
      (node (ref "3R8") (pin "1") (pinfunction "1_1") (pintype "passive"))
      (node (ref "AMP3") (pin "3") (pinfunction "+IN_A_3") (pintype "input"))
      (node (ref "X3") (pin "1") (pinfunction "1_1") (pintype "passive"))
    )
    (net (code "40") (name "Net-(AMP3-+IN_B)") (class "Default")
      (node (ref "3R5") (pin "2") (pinfunction "2_2") (pintype "passive"))
      (node (ref "AMP3") (pin "5") (pinfunction "+IN_B_5") (pintype "input"))
    )
    (net (code "41") (name "Net-(AMP3--IN_A)") (class "Default")
      (node (ref "3C1") (pin "1") (pinfunction "1_1") (pintype "passive"))
      (node (ref "3R1") (pin "2") (pinfunction "2_2") (pintype "passive"))
      (node (ref "AMP3") (pin "2") (pinfunction "-IN_A_2") (pintype "input"))
    )
    (net (code "42") (name "Net-(AMP3--IN_B)") (class "Default")
      (node (ref "3C2") (pin "2") (pinfunction "2_2") (pintype "passive"))
      (node (ref "3R4") (pin "2") (pinfunction "2_2") (pintype "passive"))
      (node (ref "AMP3") (pin "6") (pinfunction "-IN_B_6") (pintype "input"))
    )
    (net (code "43") (name "Net-(AMP3-OUT_A)") (class "Default")
      (node (ref "3R3") (pin "1") (pinfunction "1_1") (pintype "passive"))
      (node (ref "3R4") (pin "1") (pinfunction "1_1") (pintype "passive"))
      (node (ref "AMP3") (pin "1") (pinfunction "OUT_A_1") (pintype "output"))
      (node (ref "J2") (pin "2") (pinfunction "2_2") (pintype "passive"))
    )
    (net (code "44") (name "Net-(AMP3-OUT_B)") (class "Default")
      (node (ref "3C2") (pin "1") (pinfunction "1_1") (pintype "passive"))
      (node (ref "3R6") (pin "2") (pinfunction "2_2") (pintype "passive"))
      (node (ref "AMP3") (pin "7") (pinfunction "OUT_B_7") (pintype "output"))
    )
    (net (code "45") (name "Net-(AMP4-+IN_A)") (class "Default")
      (node (ref "8R23") (pin "1") (pinfunction "1_1") (pintype "passive"))
      (node (ref "AMP4") (pin "3") (pinfunction "+IN_A_3") (pintype "input"))
      (node (ref "X4") (pin "1") (pinfunction "1_1") (pintype "passive"))
    )
    (net (code "46") (name "Net-(AMP4-+IN_B)") (class "Default")
      (node (ref "8R17") (pin "2") (pinfunction "2_2") (pintype "passive"))
      (node (ref "AMP4") (pin "5") (pinfunction "+IN_B_5") (pintype "input"))
    )
    (net (code "47") (name "Net-(AMP4--IN_A)") (class "Default")
      (node (ref "8C6") (pin "1") (pinfunction "1_1") (pintype "passive"))
      (node (ref "8R24") (pin "2") (pinfunction "2_2") (pintype "passive"))
      (node (ref "AMP4") (pin "2") (pinfunction "-IN_A_2") (pintype "input"))
    )
    (net (code "48") (name "Net-(AMP4--IN_B)") (class "Default")
      (node (ref "8C5") (pin "2") (pinfunction "2_2") (pintype "passive"))
      (node (ref "8R18") (pin "2") (pinfunction "2_2") (pintype "passive"))
      (node (ref "AMP4") (pin "6") (pinfunction "-IN_B_6") (pintype "input"))
    )
    (net (code "49") (name "Net-(AMP4-OUT_A)") (class "Default")
      (node (ref "8R18") (pin "1") (pinfunction "1_1") (pintype "passive"))
      (node (ref "8R19") (pin "1") (pinfunction "1_1") (pintype "passive"))
      (node (ref "AMP4") (pin "1") (pinfunction "OUT_A_1") (pintype "output"))
      (node (ref "J2") (pin "9") (pinfunction "9_9") (pintype "passive"))
    )
    (net (code "50") (name "Net-(AMP4-OUT_B)") (class "Default")
      (node (ref "8C5") (pin "1") (pinfunction "1_1") (pintype "passive"))
      (node (ref "8R22") (pin "2") (pinfunction "2_2") (pintype "passive"))
      (node (ref "AMP4") (pin "7") (pinfunction "OUT_B_7") (pintype "output"))
    )
    (net (code "51") (name "Net-(AMP5-+IN_A)") (class "Default")
      (node (ref "5R8") (pin "1") (pinfunction "1_1") (pintype "passive"))
      (node (ref "AMP5") (pin "3") (pinfunction "+IN_A_3") (pintype "input"))
      (node (ref "X5") (pin "1") (pinfunction "1_1") (pintype "passive"))
    )
    (net (code "52") (name "Net-(AMP5-+IN_B)") (class "Default")
      (node (ref "5R5") (pin "2") (pinfunction "2_2") (pintype "passive"))
      (node (ref "AMP5") (pin "5") (pinfunction "+IN_B_5") (pintype "input"))
    )
    (net (code "53") (name "Net-(AMP5--IN_A)") (class "Default")
      (node (ref "5C1") (pin "1") (pinfunction "1_1") (pintype "passive"))
      (node (ref "5R1") (pin "2") (pinfunction "2_2") (pintype "passive"))
      (node (ref "AMP5") (pin "2") (pinfunction "-IN_A_2") (pintype "input"))
    )
    (net (code "54") (name "Net-(AMP5--IN_B)") (class "Default")
      (node (ref "5C2") (pin "2") (pinfunction "2_2") (pintype "passive"))
      (node (ref "5R4") (pin "2") (pinfunction "2_2") (pintype "passive"))
      (node (ref "AMP5") (pin "6") (pinfunction "-IN_B_6") (pintype "input"))
    )
    (net (code "55") (name "Net-(AMP5-OUT_A)") (class "Default")
      (node (ref "5R3") (pin "1") (pinfunction "1_1") (pintype "passive"))
      (node (ref "5R4") (pin "1") (pinfunction "1_1") (pintype "passive"))
      (node (ref "AMP5") (pin "1") (pinfunction "OUT_A_1") (pintype "output"))
      (node (ref "J3") (pin "2") (pinfunction "2_2") (pintype "passive"))
    )
    (net (code "56") (name "Net-(AMP5-OUT_B)") (class "Default")
      (node (ref "5C2") (pin "1") (pinfunction "1_1") (pintype "passive"))
      (node (ref "5R6") (pin "2") (pinfunction "2_2") (pintype "passive"))
      (node (ref "AMP5") (pin "7") (pinfunction "OUT_B_7") (pintype "output"))
    )
    (net (code "57") (name "Net-(AMP6-+IN_A)") (class "Default")
      (node (ref "8R15") (pin "1") (pinfunction "1_1") (pintype "passive"))
      (node (ref "AMP6") (pin "3") (pinfunction "+IN_A_3") (pintype "input"))
      (node (ref "X6") (pin "1") (pinfunction "1_1") (pintype "passive"))
    )
    (net (code "58") (name "Net-(AMP6-+IN_B)") (class "Default")
      (node (ref "8R9") (pin "2") (pinfunction "2_2") (pintype "passive"))
      (node (ref "AMP6") (pin "5") (pinfunction "+IN_B_5") (pintype "input"))
    )
    (net (code "59") (name "Net-(AMP6--IN_A)") (class "Default")
      (node (ref "8C4") (pin "1") (pinfunction "1_1") (pintype "passive"))
      (node (ref "8R16") (pin "2") (pinfunction "2_2") (pintype "passive"))
      (node (ref "AMP6") (pin "2") (pinfunction "-IN_A_2") (pintype "input"))
    )
    (net (code "60") (name "Net-(AMP6--IN_B)") (class "Default")
      (node (ref "8C3") (pin "2") (pinfunction "2_2") (pintype "passive"))
      (node (ref "8R10") (pin "2") (pinfunction "2_2") (pintype "passive"))
      (node (ref "AMP6") (pin "6") (pinfunction "-IN_B_6") (pintype "input"))
    )
    (net (code "61") (name "Net-(AMP6-OUT_A)") (class "Default")
      (node (ref "8R10") (pin "1") (pinfunction "1_1") (pintype "passive"))
      (node (ref "8R11") (pin "1") (pinfunction "1_1") (pintype "passive"))
      (node (ref "AMP6") (pin "1") (pinfunction "OUT_A_1") (pintype "output"))
      (node (ref "J3") (pin "9") (pinfunction "9_9") (pintype "passive"))
    )
    (net (code "62") (name "Net-(AMP6-OUT_B)") (class "Default")
      (node (ref "8C3") (pin "1") (pinfunction "1_1") (pintype "passive"))
      (node (ref "8R14") (pin "2") (pinfunction "2_2") (pintype "passive"))
      (node (ref "AMP6") (pin "7") (pinfunction "OUT_B_7") (pintype "output"))
    )
    (net (code "63") (name "Net-(AMP7-+IN_A)") (class "Default")
      (node (ref "7R8") (pin "1") (pinfunction "1_1") (pintype "passive"))
      (node (ref "AMP7") (pin "3") (pinfunction "+IN_A_3") (pintype "input"))
      (node (ref "X7") (pin "1") (pinfunction "1_1") (pintype "passive"))
    )
    (net (code "64") (name "Net-(AMP7-+IN_B)") (class "Default")
      (node (ref "7R5") (pin "2") (pinfunction "2_2") (pintype "passive"))
      (node (ref "AMP7") (pin "5") (pinfunction "+IN_B_5") (pintype "input"))
    )
    (net (code "65") (name "Net-(AMP7--IN_A)") (class "Default")
      (node (ref "7C1") (pin "1") (pinfunction "1_1") (pintype "passive"))
      (node (ref "7R1") (pin "2") (pinfunction "2_2") (pintype "passive"))
      (node (ref "AMP7") (pin "2") (pinfunction "-IN_A_2") (pintype "input"))
    )
    (net (code "66") (name "Net-(AMP7--IN_B)") (class "Default")
      (node (ref "7C2") (pin "2") (pinfunction "2_2") (pintype "passive"))
      (node (ref "7R4") (pin "2") (pinfunction "2_2") (pintype "passive"))
      (node (ref "AMP7") (pin "6") (pinfunction "-IN_B_6") (pintype "input"))
    )
    (net (code "67") (name "Net-(AMP7-OUT_A)") (class "Default")
      (node (ref "7R3") (pin "1") (pinfunction "1_1") (pintype "passive"))
      (node (ref "7R4") (pin "1") (pinfunction "1_1") (pintype "passive"))
      (node (ref "AMP7") (pin "1") (pinfunction "OUT_A_1") (pintype "output"))
      (node (ref "J4") (pin "2") (pinfunction "2_2") (pintype "passive"))
    )
    (net (code "68") (name "Net-(AMP7-OUT_B)") (class "Default")
      (node (ref "7C2") (pin "1") (pinfunction "1_1") (pintype "passive"))
      (node (ref "7R6") (pin "2") (pinfunction "2_2") (pintype "passive"))
      (node (ref "AMP7") (pin "7") (pinfunction "OUT_B_7") (pintype "output"))
    )
    (net (code "69") (name "Net-(AMP8-+IN_A)") (class "Default")
      (node (ref "8R8") (pin "1") (pinfunction "1_1") (pintype "passive"))
      (node (ref "AMP8") (pin "3") (pinfunction "+IN_A_3") (pintype "input"))
      (node (ref "X8") (pin "1") (pinfunction "1_1") (pintype "passive"))
    )
    (net (code "70") (name "Net-(AMP8-+IN_B)") (class "Default")
      (node (ref "8R5") (pin "2") (pinfunction "2_2") (pintype "passive"))
      (node (ref "AMP8") (pin "5") (pinfunction "+IN_B_5") (pintype "input"))
    )
    (net (code "71") (name "Net-(AMP8--IN_A)") (class "Default")
      (node (ref "8C1") (pin "1") (pinfunction "1_1") (pintype "passive"))
      (node (ref "8R1") (pin "2") (pinfunction "2_2") (pintype "passive"))
      (node (ref "AMP8") (pin "2") (pinfunction "-IN_A_2") (pintype "input"))
    )
    (net (code "72") (name "Net-(AMP8--IN_B)") (class "Default")
      (node (ref "8C2") (pin "2") (pinfunction "2_2") (pintype "passive"))
      (node (ref "8R4") (pin "2") (pinfunction "2_2") (pintype "passive"))
      (node (ref "AMP8") (pin "6") (pinfunction "-IN_B_6") (pintype "input"))
    )
    (net (code "73") (name "Net-(AMP8-OUT_A)") (class "Default")
      (node (ref "8R3") (pin "1") (pinfunction "1_1") (pintype "passive"))
      (node (ref "8R4") (pin "1") (pinfunction "1_1") (pintype "passive"))
      (node (ref "AMP8") (pin "1") (pinfunction "OUT_A_1") (pintype "output"))
      (node (ref "J4") (pin "9") (pinfunction "9_9") (pintype "passive"))
    )
    (net (code "74") (name "Net-(AMP8-OUT_B)") (class "Default")
      (node (ref "8C2") (pin "1") (pinfunction "1_1") (pintype "passive"))
      (node (ref "8R6") (pin "2") (pinfunction "2_2") (pintype "passive"))
      (node (ref "AMP8") (pin "7") (pinfunction "OUT_B_7") (pintype "output"))
    )
    (net (code "75") (name "Net-(AUX_POWER-C)") (class "Default")
      (node (ref "AUX_POWER") (pin "K") (pinfunction "C_K") (pintype "passive"))
      (node (ref "R1") (pin "1") (pinfunction "1_1") (pintype "passive"))
    )
    (net (code "76") (name "Net-(BBB-C)") (class "Default")
      (node (ref "BBB") (pin "K") (pinfunction "C_K") (pintype "passive"))
      (node (ref "R2") (pin "1") (pinfunction "1_1") (pintype "passive"))
    )
    (net (code "77") (name "Net-(BBB-PadA)") (class "Default")
      (node (ref "BBB") (pin "A") (pinfunction "A_A") (pintype "passive"))
      (node (ref "J5") (pin "5") (pinfunction "5_5") (pintype "passive"))
    )
    (net (code "78") (name "Net-(F1-2)") (class "Default")
      (node (ref "F1") (pin "P$2") (pinfunction "2_P$2") (pintype "passive"))
      (node (ref "J6") (pin "2") (pinfunction "V+_2") (pintype "power_in"))
    )
    (net (code "79") (name "Net-(J5-Pad1)") (class "Default")
      (node (ref "J5") (pin "1") (pinfunction "1_1") (pintype "passive"))
      (node (ref "REC") (pin "A") (pinfunction "A_A") (pintype "passive"))
    )
    (net (code "80") (name "Net-(J5-Pad2)") (class "Default")
      (node (ref "J5") (pin "2") (pinfunction "2_2") (pintype "passive"))
      (node (ref "REC/STOP") (pin "3") (pinfunction "3_3") (pintype "passive"))
    )
    (net (code "81") (name "Net-(J5-Pad3)") (class "Default")
      (node (ref "J5") (pin "3") (pinfunction "3_3") (pintype "passive"))
      (node (ref "REC/STOP") (pin "1") (pinfunction "1_1") (pintype "passive"))
    )
    (net (code "82") (name "Net-(J5-Pad4)") (class "Default")
      (node (ref "J5") (pin "4") (pinfunction "4_4") (pintype "passive"))
      (node (ref "ON/OFF") (pin "2") (pinfunction "2_2") (pintype "passive"))
    )
    (net (code "83") (name "Net-(REC-C)") (class "Default")
      (node (ref "R3") (pin "1") (pinfunction "1_1") (pintype "passive"))
      (node (ref "REC") (pin "K") (pinfunction "C_K") (pintype "passive"))
    )
    (net (code "84") (name "SUPPLY1_V+") (class "Default")
      (node (ref "AUX_POWER") (pin "A") (pinfunction "A_A") (pintype "passive"))
      (node (ref "F1") (pin "P$1") (pinfunction "1_P$1") (pintype "passive"))
      (node (ref "J7") (pin "2") (pinfunction "V+_2") (pintype "power_in"))
    )
    (net (code "85") (name "SUPPLY2_GND") (class "Default")
      (node (ref "J6") (pin "1") (pinfunction "GND_1") (pintype "power_in"))
      (node (ref "J7") (pin "1") (pinfunction "GND_1") (pintype "power_in"))
      (node (ref "ON/OFF") (pin "3") (pinfunction "3_3") (pintype "passive"))
      (node (ref "R1") (pin "2") (pinfunction "2_2") (pintype "passive"))
      (node (ref "R2") (pin "2") (pinfunction "2_2") (pintype "passive"))
      (node (ref "R3") (pin "2") (pinfunction "2_2") (pintype "passive"))
    )
    (net (code "86") (name "unconnected-(J1-Pad3)") (class "Default")
      (node (ref "J1") (pin "3") (pinfunction "3_3") (pintype "passive"))
    )
    (net (code "87") (name "unconnected-(J1-Pad4)") (class "Default")
      (node (ref "J1") (pin "4") (pinfunction "4_4") (pintype "passive"))
    )
    (net (code "88") (name "unconnected-(J1-Pad5)") (class "Default")
      (node (ref "J1") (pin "5") (pinfunction "5_5") (pintype "passive"))
    )
    (net (code "89") (name "unconnected-(J1-Pad7)") (class "Default")
      (node (ref "J1") (pin "7") (pinfunction "7_7") (pintype "passive"))
    )
    (net (code "90") (name "unconnected-(J1-Pad10)") (class "Default")
      (node (ref "J1") (pin "10") (pinfunction "10_10") (pintype "passive"))
    )
    (net (code "91") (name "unconnected-(J1-Pad11)") (class "Default")
      (node (ref "J1") (pin "11") (pinfunction "11_11") (pintype "passive"))
    )
    (net (code "92") (name "unconnected-(J1-Pad12)") (class "Default")
      (node (ref "J1") (pin "12") (pinfunction "12_12") (pintype "passive"))
    )
    (net (code "93") (name "unconnected-(J2-Pad3)") (class "Default")
      (node (ref "J2") (pin "3") (pinfunction "3_3") (pintype "passive"))
    )
    (net (code "94") (name "unconnected-(J2-Pad4)") (class "Default")
      (node (ref "J2") (pin "4") (pinfunction "4_4") (pintype "passive"))
    )
    (net (code "95") (name "unconnected-(J2-Pad5)") (class "Default")
      (node (ref "J2") (pin "5") (pinfunction "5_5") (pintype "passive"))
    )
    (net (code "96") (name "unconnected-(J2-Pad7)") (class "Default")
      (node (ref "J2") (pin "7") (pinfunction "7_7") (pintype "passive"))
    )
    (net (code "97") (name "unconnected-(J2-Pad10)") (class "Default")
      (node (ref "J2") (pin "10") (pinfunction "10_10") (pintype "passive"))
    )
    (net (code "98") (name "unconnected-(J2-Pad11)") (class "Default")
      (node (ref "J2") (pin "11") (pinfunction "11_11") (pintype "passive"))
    )
    (net (code "99") (name "unconnected-(J2-Pad12)") (class "Default")
      (node (ref "J2") (pin "12") (pinfunction "12_12") (pintype "passive"))
    )
    (net (code "100") (name "unconnected-(J3-Pad3)") (class "Default")
      (node (ref "J3") (pin "3") (pinfunction "3_3") (pintype "passive"))
    )
    (net (code "101") (name "unconnected-(J3-Pad4)") (class "Default")
      (node (ref "J3") (pin "4") (pinfunction "4_4") (pintype "passive"))
    )
    (net (code "102") (name "unconnected-(J3-Pad5)") (class "Default")
      (node (ref "J3") (pin "5") (pinfunction "5_5") (pintype "passive"))
    )
    (net (code "103") (name "unconnected-(J3-Pad7)") (class "Default")
      (node (ref "J3") (pin "7") (pinfunction "7_7") (pintype "passive"))
    )
    (net (code "104") (name "unconnected-(J3-Pad10)") (class "Default")
      (node (ref "J3") (pin "10") (pinfunction "10_10") (pintype "passive"))
    )
    (net (code "105") (name "unconnected-(J3-Pad11)") (class "Default")
      (node (ref "J3") (pin "11") (pinfunction "11_11") (pintype "passive"))
    )
    (net (code "106") (name "unconnected-(J3-Pad12)") (class "Default")
      (node (ref "J3") (pin "12") (pinfunction "12_12") (pintype "passive"))
    )
    (net (code "107") (name "unconnected-(J4-Pad3)") (class "Default")
      (node (ref "J4") (pin "3") (pinfunction "3_3") (pintype "passive"))
    )
    (net (code "108") (name "unconnected-(J4-Pad4)") (class "Default")
      (node (ref "J4") (pin "4") (pinfunction "4_4") (pintype "passive"))
    )
    (net (code "109") (name "unconnected-(J4-Pad5)") (class "Default")
      (node (ref "J4") (pin "5") (pinfunction "5_5") (pintype "passive"))
    )
    (net (code "110") (name "unconnected-(J4-Pad7)") (class "Default")
      (node (ref "J4") (pin "7") (pinfunction "7_7") (pintype "passive"))
    )
    (net (code "111") (name "unconnected-(J4-Pad10)") (class "Default")
      (node (ref "J4") (pin "10") (pinfunction "10_10") (pintype "passive"))
    )
    (net (code "112") (name "unconnected-(J4-Pad11)") (class "Default")
      (node (ref "J4") (pin "11") (pinfunction "11_11") (pintype "passive"))
    )
    (net (code "113") (name "unconnected-(J4-Pad12)") (class "Default")
      (node (ref "J4") (pin "12") (pinfunction "12_12") (pintype "passive"))
    )
    (net (code "114") (name "unconnected-(ON/OFF-Pad1)") (class "Default")
      (node (ref "ON/OFF") (pin "1") (pinfunction "1_1") (pintype "passive"))
    )
    (net (code "115") (name "unconnected-(ON/OFF-Pad4)") (class "Default")
      (node (ref "ON/OFF") (pin "4") (pinfunction "4_4") (pintype "passive"))
    )
    (net (code "116") (name "unconnected-(REC/STOP-Pad2)") (class "Default")
      (node (ref "REC/STOP") (pin "2") (pinfunction "2_2") (pintype "passive"))
    )
    (net (code "117") (name "unconnected-(REC/STOP-Pad4)") (class "Default")
      (node (ref "REC/STOP") (pin "4") (pinfunction "4_4") (pintype "passive"))
    )
  )
)
